# MPU_9250.net
KiCad netlist of a schematic drawn in Altium Designer
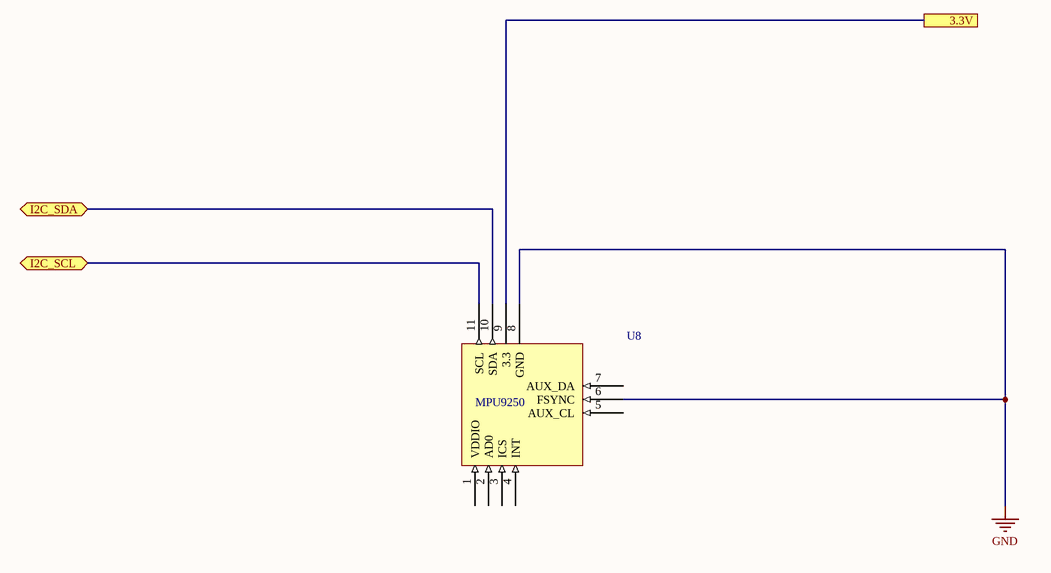
[diagram p0: MPU 9250.SchDoc]

(export (version "E")
  (design (tool "Eeschema 10.0.6"))
  (components
    (comp (ref "U8")
      (value "~")
      (footprint "CB_PERIFÉRICOS:MPU-9250_CONECTOR")
      (description "SPARKFUN MPU9250 GYROSCOPE")
      (libsource (lib "altium-import") (part "root_0__MPU-9250_CONECTOR.SchLib"))
    )
  )
  (nets
    (net (code "1") (name "/3.3V") (class "Default")
      (node (ref "U8") (pin "9") (pinfunction "3.3_9") (pintype "power_in"))
    )
    (net (code "2") (name "/I2C_SCL") (class "Default")
      (node (ref "U8") (pin "11") (pinfunction "SCL_11") (pintype "output"))
    )
    (net (code "3") (name "/I2C_SDA") (class "Default")
      (node (ref "U8") (pin "10") (pinfunction "SDA_10") (pintype "output"))
    )
    (net (code "4") (name "GND") (class "Default")
      (node (ref "U8") (pin "6") (pinfunction "FSYNC_6") (pintype "input"))
      (node (ref "U8") (pin "8") (pinfunction "GND_8") (pintype "power_in"))
    )
    (net (code "5") (name "unconnected-(U8-AD0-Pad2)") (class "Default")
      (node (ref "U8") (pin "2") (pinfunction "AD0_2") (pintype "input"))
    )
    (net (code "6") (name "unconnected-(U8-AUX_CL-Pad5)") (class "Default")
      (node (ref "U8") (pin "5") (pinfunction "AUX_CL_5") (pintype "input"))
    )
    (net (code "7") (name "unconnected-(U8-AUX_DA-Pad7)") (class "Default")
      (node (ref "U8") (pin "7") (pinfunction "AUX_DA_7") (pintype "input"))
    )
    (net (code "8") (name "unconnected-(U8-ICS-Pad3)") (class "Default")
      (node (ref "U8") (pin "3") (pinfunction "ICS_3") (pintype "input"))
    )
    (net (code "9") (name "unconnected-(U8-INT-Pad4)") (class "Default")
      (node (ref "U8") (pin "4") (pinfunction "INT_4") (pintype "input"))
    )
    (net (code "10") (name "unconnected-(U8-VDDIO-Pad1)") (class "Default")
      (node (ref "U8") (pin "1") (pinfunction "VDDIO_1") (pintype "input"))
    )
  )
)
